# Laser_Harp_PCB.net
KiCad netlist of a schematic drawn in EAGLE
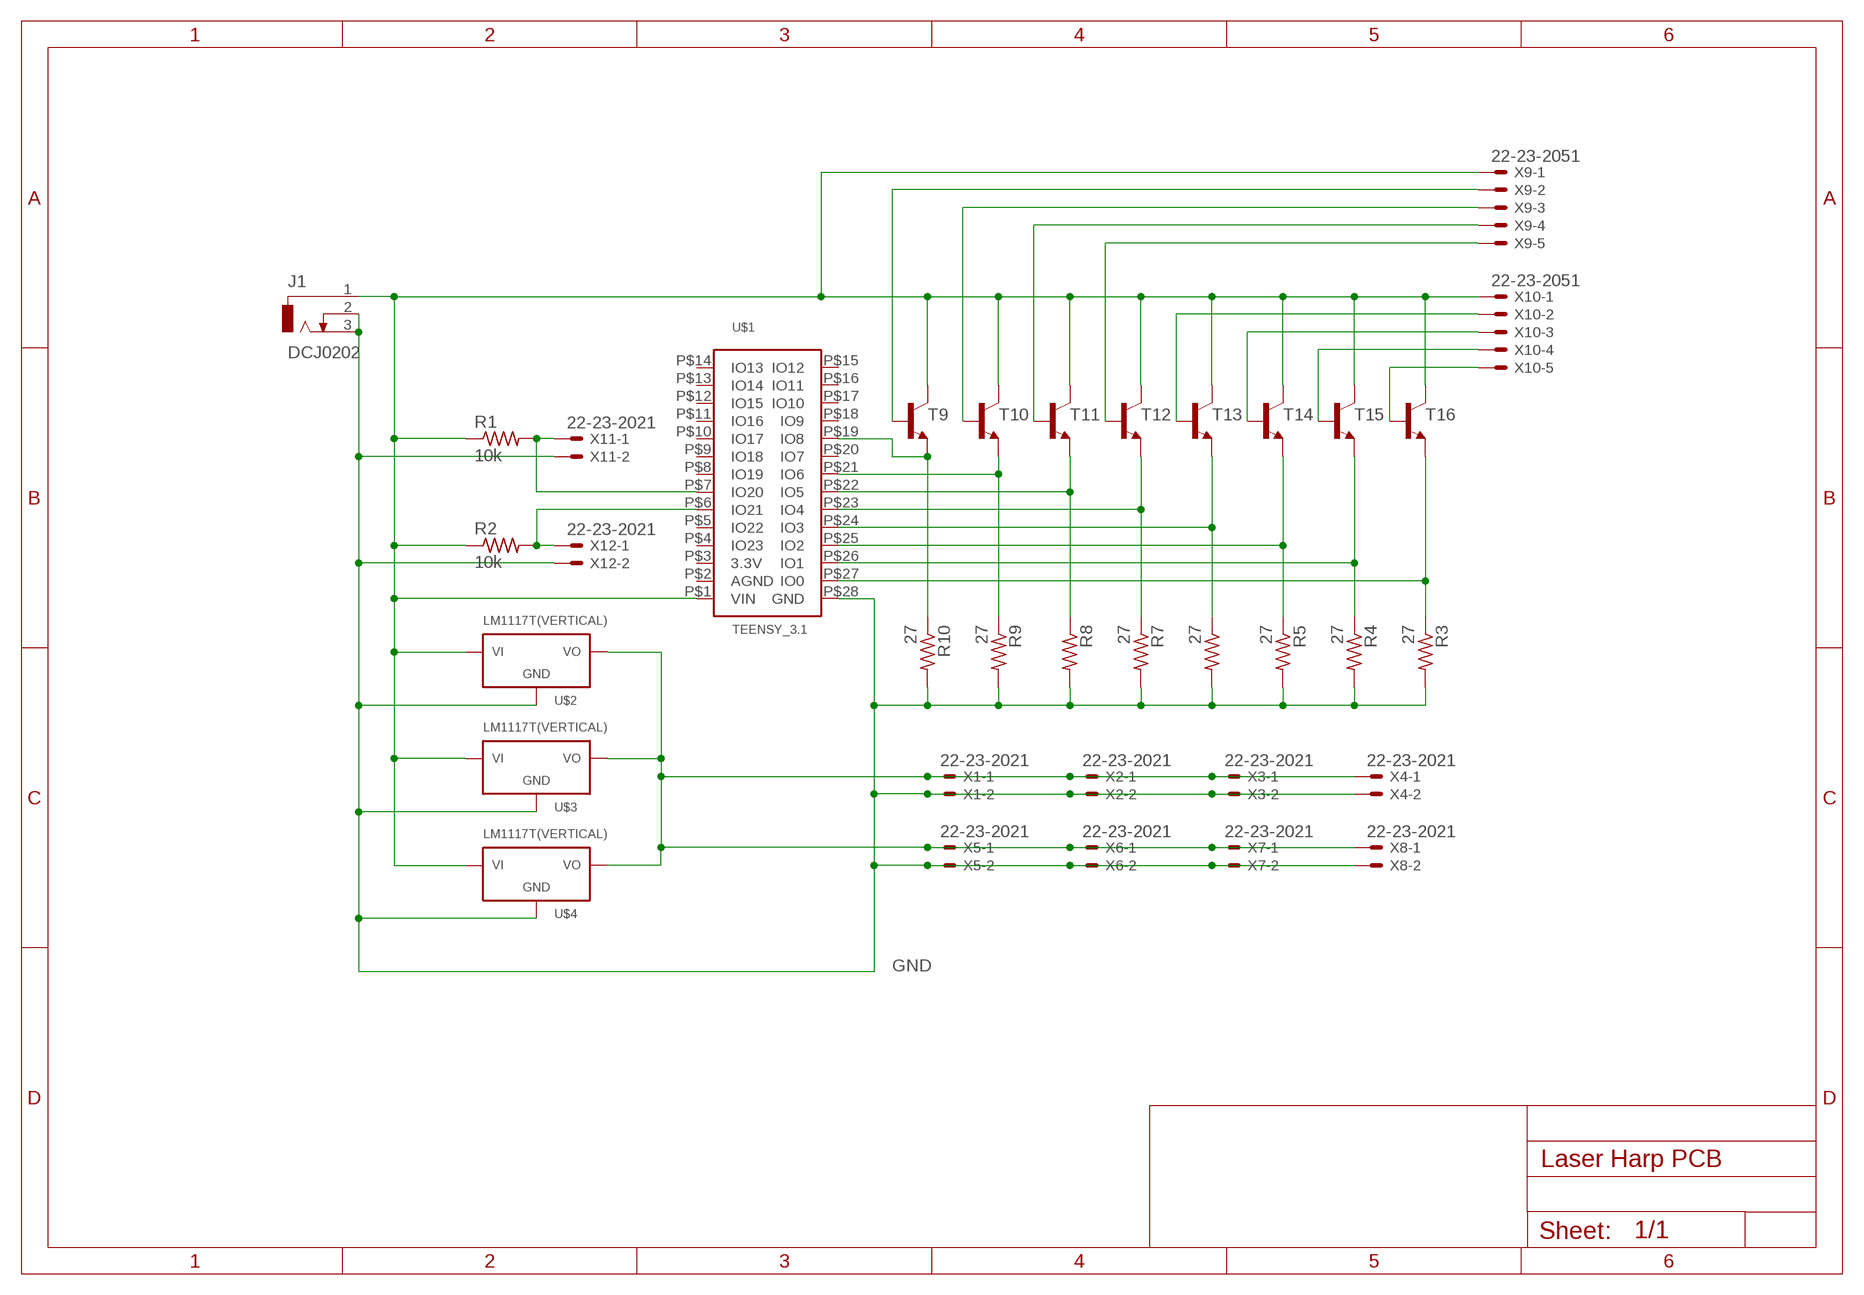
[diagram p0: schematic, sheet 1]

(export (version "E")
  (design (tool "Eeschema 10.0.6"))
  (components
    (comp (ref "J1")
      (value "DCJ0202")
      (footprint "eagle-import:DCJ0202")
      (libsource (lib "eagle-import") (part "DCJ0202"))
    )
    (comp (ref "R1")
      (value "10k")
      (footprint "eagle-import:0207_7")
      (libsource (lib "eagle-import") (part "R-US_0207/7"))
    )
    (comp (ref "R2")
      (value "10k")
      (footprint "eagle-import:0207_7")
      (libsource (lib "eagle-import") (part "R-US_0207/7"))
    )
    (comp (ref "R3")
      (value "27")
      (footprint "eagle-import:0207_7")
      (libsource (lib "eagle-import") (part "R-US_0207/7"))
    )
    (comp (ref "R4")
      (value "27")
      (footprint "eagle-import:0207_7")
      (libsource (lib "eagle-import") (part "R-US_0207/7"))
    )
    (comp (ref "R5")
      (value "27")
      (footprint "eagle-import:0207_7")
      (libsource (lib "eagle-import") (part "R-US_0207/7"))
    )
    (comp (ref "R6")
      (value "27")
      (footprint "eagle-import:0207_7")
      (libsource (lib "eagle-import") (part "R-US_0207/7"))
    )
    (comp (ref "R7")
      (value "27")
      (footprint "eagle-import:0207_7")
      (libsource (lib "eagle-import") (part "R-US_0207/7"))
    )
    (comp (ref "R8")
      (value "27")
      (footprint "eagle-import:0207_7")
      (libsource (lib "eagle-import") (part "R-US_0207/7"))
    )
    (comp (ref "R9")
      (value "27")
      (footprint "eagle-import:0207_7")
      (libsource (lib "eagle-import") (part "R-US_0207/7"))
    )
    (comp (ref "R10")
      (value "27")
      (footprint "eagle-import:0207_7")
      (libsource (lib "eagle-import") (part "R-US_0207/7"))
    )
    (comp (ref "T9")
      (value "2N3904-NPN-TO92-EBC")
      (footprint "eagle-import:TO92-EBC")
      (libsource (lib "eagle-import") (part "-NPN-TO92-EBC2N3904"))
    )
    (comp (ref "T10")
      (value "2N3904-NPN-TO92-EBC")
      (footprint "eagle-import:TO92-EBC")
      (libsource (lib "eagle-import") (part "-NPN-TO92-EBC2N3904"))
    )
    (comp (ref "T11")
      (value "2N3904-NPN-TO92-EBC")
      (footprint "eagle-import:TO92-EBC")
      (libsource (lib "eagle-import") (part "-NPN-TO92-EBC2N3904"))
    )
    (comp (ref "T12")
      (value "2N3904-NPN-TO92-EBC")
      (footprint "eagle-import:TO92-EBC")
      (libsource (lib "eagle-import") (part "-NPN-TO92-EBC2N3904"))
    )
    (comp (ref "T13")
      (value "2N3904-NPN-TO92-EBC")
      (footprint "eagle-import:TO92-EBC")
      (libsource (lib "eagle-import") (part "-NPN-TO92-EBC2N3904"))
    )
    (comp (ref "T14")
      (value "2N3904-NPN-TO92-EBC")
      (footprint "eagle-import:TO92-EBC")
      (libsource (lib "eagle-import") (part "-NPN-TO92-EBC2N3904"))
    )
    (comp (ref "T15")
      (value "2N3904-NPN-TO92-EBC")
      (footprint "eagle-import:TO92-EBC")
      (libsource (lib "eagle-import") (part "-NPN-TO92-EBC2N3904"))
    )
    (comp (ref "T16")
      (value "2N3904-NPN-TO92-EBC")
      (footprint "eagle-import:TO92-EBC")
      (libsource (lib "eagle-import") (part "-NPN-TO92-EBC2N3904"))
    )
    (comp (ref "U$1")
      (value "TEENSY_3.1")
      (footprint "eagle-import:TEENSY_3.1")
      (libsource (lib "eagle-import") (part "TEENSY_3.1"))
    )
    (comp (ref "U$2")
      (value "LM1117T(VERTICAL)")
      (footprint "eagle-import:317TS")
      (libsource (lib "eagle-import") (part "LM1117T(VERTICAL)"))
    )
    (comp (ref "U$3")
      (value "LM1117T(VERTICAL)")
      (footprint "eagle-import:317TS")
      (libsource (lib "eagle-import") (part "LM1117T(VERTICAL)"))
    )
    (comp (ref "U$4")
      (value "LM1117T(VERTICAL)")
      (footprint "eagle-import:317TS")
      (libsource (lib "eagle-import") (part "LM1117T(VERTICAL)"))
    )
    (comp (ref "X1")
      (value "22-23-2021")
      (footprint "eagle-import:22-23-2021")
      (fields (field (name "MF") "MOLEX"))
      (libsource (lib "eagle-import") (part "22-23-2021"))
    )
    (comp (ref "X2")
      (value "22-23-2021")
      (footprint "eagle-import:22-23-2021")
      (fields (field (name "MF") "MOLEX"))
      (libsource (lib "eagle-import") (part "22-23-2021"))
    )
    (comp (ref "X3")
      (value "22-23-2021")
      (footprint "eagle-import:22-23-2021")
      (fields (field (name "MF") "MOLEX"))
      (libsource (lib "eagle-import") (part "22-23-2021"))
    )
    (comp (ref "X4")
      (value "22-23-2021")
      (footprint "eagle-import:22-23-2021")
      (fields (field (name "MF") "MOLEX"))
      (libsource (lib "eagle-import") (part "22-23-2021"))
    )
    (comp (ref "X5")
      (value "22-23-2021")
      (footprint "eagle-import:22-23-2021")
      (fields (field (name "MF") "MOLEX"))
      (libsource (lib "eagle-import") (part "22-23-2021"))
    )
    (comp (ref "X6")
      (value "22-23-2021")
      (footprint "eagle-import:22-23-2021")
      (fields (field (name "MF") "MOLEX"))
      (libsource (lib "eagle-import") (part "22-23-2021"))
    )
    (comp (ref "X7")
      (value "22-23-2021")
      (footprint "eagle-import:22-23-2021")
      (fields (field (name "MF") "MOLEX"))
      (libsource (lib "eagle-import") (part "22-23-2021"))
    )
    (comp (ref "X8")
      (value "22-23-2021")
      (footprint "eagle-import:22-23-2021")
      (fields (field (name "MF") "MOLEX"))
      (libsource (lib "eagle-import") (part "22-23-2021"))
    )
    (comp (ref "X9")
      (value "22-23-2051")
      (footprint "eagle-import:22-23-2051")
      (fields (field (name "MF") "MOLEX"))
      (libsource (lib "eagle-import") (part "22-23-2051"))
    )
    (comp (ref "X10")
      (value "22-23-2051")
      (footprint "eagle-import:22-23-2051")
      (fields (field (name "MF") "MOLEX"))
      (libsource (lib "eagle-import") (part "22-23-2051"))
    )
    (comp (ref "X11")
      (value "22-23-2021")
      (footprint "eagle-import:22-23-2021")
      (fields (field (name "MF") "MOLEX"))
      (libsource (lib "eagle-import") (part "22-23-2021"))
    )
    (comp (ref "X12")
      (value "22-23-2021")
      (footprint "eagle-import:22-23-2021")
      (fields (field (name "MF") "MOLEX"))
      (libsource (lib "eagle-import") (part "22-23-2021"))
    )
  )
  (nets
    (net (code "1") (name "/GND") (class "Default")
      (node (ref "J1") (pin "2") (pinfunction "2_2") (pintype "passive"))
      (node (ref "J1") (pin "3") (pinfunction "3_3") (pintype "passive"))
      (node (ref "R10") (pin "2") (pinfunction "2_2") (pintype "passive"))
      (node (ref "R3") (pin "2") (pinfunction "2_2") (pintype "passive"))
      (node (ref "R4") (pin "2") (pinfunction "2_2") (pintype "passive"))
      (node (ref "R5") (pin "2") (pinfunction "2_2") (pintype "passive"))
      (node (ref "R6") (pin "2") (pinfunction "2_2") (pintype "passive"))
      (node (ref "R7") (pin "2") (pinfunction "2_2") (pintype "passive"))
      (node (ref "R8") (pin "2") (pinfunction "2_2") (pintype "passive"))
      (node (ref "R9") (pin "2") (pinfunction "2_2") (pintype "passive"))
      (node (ref "U$1") (pin "P$28") (pinfunction "GND_P$28") (pintype "bidirectional"))
      (node (ref "U$2") (pin "1") (pinfunction "GND_1") (pintype "bidirectional"))
      (node (ref "U$3") (pin "1") (pinfunction "GND_1") (pintype "bidirectional"))
      (node (ref "U$4") (pin "1") (pinfunction "GND_1") (pintype "bidirectional"))
      (node (ref "X1") (pin "2") (pinfunction "S_2") (pintype "passive"))
      (node (ref "X11") (pin "2") (pinfunction "S_2") (pintype "passive"))
      (node (ref "X12") (pin "2") (pinfunction "S_2") (pintype "passive"))
      (node (ref "X2") (pin "2") (pinfunction "S_2") (pintype "passive"))
      (node (ref "X3") (pin "2") (pinfunction "S_2") (pintype "passive"))
      (node (ref "X4") (pin "2") (pinfunction "S_2") (pintype "passive"))
      (node (ref "X5") (pin "2") (pinfunction "S_2") (pintype "passive"))
      (node (ref "X6") (pin "2") (pinfunction "S_2") (pintype "passive"))
      (node (ref "X7") (pin "2") (pinfunction "S_2") (pintype "passive"))
      (node (ref "X8") (pin "2") (pinfunction "S_2") (pintype "passive"))
    )
    (net (code "2") (name "Net-(U$1-IO0)") (class "Default")
      (node (ref "R3") (pin "1") (pinfunction "1_1") (pintype "passive"))
      (node (ref "T16") (pin "E") (pinfunction "E_E") (pintype "passive"))
      (node (ref "U$1") (pin "P$27") (pinfunction "IO0_P$27") (pintype "bidirectional"))
    )
    (net (code "3") (name "Net-(U$1-IO1)") (class "Default")
      (node (ref "R4") (pin "1") (pinfunction "1_1") (pintype "passive"))
      (node (ref "T15") (pin "E") (pinfunction "E_E") (pintype "passive"))
      (node (ref "U$1") (pin "P$26") (pinfunction "IO1_P$26") (pintype "bidirectional"))
    )
    (net (code "4") (name "Net-(U$1-IO2)") (class "Default")
      (node (ref "R5") (pin "1") (pinfunction "1_1") (pintype "passive"))
      (node (ref "T14") (pin "E") (pinfunction "E_E") (pintype "passive"))
      (node (ref "U$1") (pin "P$25") (pinfunction "IO2_P$25") (pintype "bidirectional"))
    )
    (net (code "5") (name "Net-(U$1-IO3)") (class "Default")
      (node (ref "R6") (pin "1") (pinfunction "1_1") (pintype "passive"))
      (node (ref "T13") (pin "E") (pinfunction "E_E") (pintype "passive"))
      (node (ref "U$1") (pin "P$24") (pinfunction "IO3_P$24") (pintype "bidirectional"))
    )
    (net (code "6") (name "Net-(U$1-IO4)") (class "Default")
      (node (ref "R7") (pin "1") (pinfunction "1_1") (pintype "passive"))
      (node (ref "T12") (pin "E") (pinfunction "E_E") (pintype "passive"))
      (node (ref "U$1") (pin "P$23") (pinfunction "IO4_P$23") (pintype "bidirectional"))
    )
    (net (code "7") (name "Net-(U$1-IO5)") (class "Default")
      (node (ref "R8") (pin "1") (pinfunction "1_1") (pintype "passive"))
      (node (ref "T11") (pin "E") (pinfunction "E_E") (pintype "passive"))
      (node (ref "U$1") (pin "P$22") (pinfunction "IO5_P$22") (pintype "bidirectional"))
    )
    (net (code "8") (name "Net-(U$1-IO6)") (class "Default")
      (node (ref "R9") (pin "1") (pinfunction "1_1") (pintype "passive"))
      (node (ref "T10") (pin "E") (pinfunction "E_E") (pintype "passive"))
      (node (ref "U$1") (pin "P$21") (pinfunction "IO6_P$21") (pintype "bidirectional"))
    )
    (net (code "9") (name "Net-(U$1-IO8)") (class "Default")
      (node (ref "R10") (pin "1") (pinfunction "1_1") (pintype "passive"))
      (node (ref "T9") (pin "E") (pinfunction "E_E") (pintype "passive"))
      (node (ref "U$1") (pin "P$19") (pinfunction "IO8_P$19") (pintype "bidirectional"))
    )
    (net (code "10") (name "Net-(U$1-IO20)") (class "Default")
      (node (ref "R1") (pin "2") (pinfunction "2_2") (pintype "passive"))
      (node (ref "U$1") (pin "P$7") (pinfunction "IO20_P$7") (pintype "bidirectional"))
      (node (ref "X11") (pin "1") (pinfunction "S_1") (pintype "passive"))
    )
    (net (code "11") (name "Net-(U$1-IO21)") (class "Default")
      (node (ref "R2") (pin "2") (pinfunction "2_2") (pintype "passive"))
      (node (ref "U$1") (pin "P$6") (pinfunction "IO21_P$6") (pintype "bidirectional"))
      (node (ref "X12") (pin "1") (pinfunction "S_1") (pintype "passive"))
    )
    (net (code "12") (name "Net-(U$1-VIN)") (class "Default")
      (node (ref "J1") (pin "1") (pinfunction "1_1") (pintype "passive"))
      (node (ref "R1") (pin "1") (pinfunction "1_1") (pintype "passive"))
      (node (ref "R2") (pin "1") (pinfunction "1_1") (pintype "passive"))
      (node (ref "T10") (pin "C") (pinfunction "C_C") (pintype "passive"))
      (node (ref "T11") (pin "C") (pinfunction "C_C") (pintype "passive"))
      (node (ref "T12") (pin "C") (pinfunction "C_C") (pintype "passive"))
      (node (ref "T13") (pin "C") (pinfunction "C_C") (pintype "passive"))
      (node (ref "T14") (pin "C") (pinfunction "C_C") (pintype "passive"))
      (node (ref "T15") (pin "C") (pinfunction "C_C") (pintype "passive"))
      (node (ref "T16") (pin "C") (pinfunction "C_C") (pintype "passive"))
      (node (ref "T9") (pin "C") (pinfunction "C_C") (pintype "passive"))
      (node (ref "U$1") (pin "P$1") (pinfunction "VIN_P$1") (pintype "bidirectional"))
      (node (ref "U$2") (pin "3") (pinfunction "VIN_3") (pintype "bidirectional"))
      (node (ref "U$3") (pin "3") (pinfunction "VIN_3") (pintype "bidirectional"))
      (node (ref "U$4") (pin "3") (pinfunction "VIN_3") (pintype "bidirectional"))
      (node (ref "X10") (pin "1") (pinfunction "S_1") (pintype "passive"))
      (node (ref "X9") (pin "1") (pinfunction "S_1") (pintype "passive"))
    )
    (net (code "13") (name "Net-(U$2-VOUT)") (class "Default")
      (node (ref "U$2") (pin "2") (pinfunction "VOUT_2") (pintype "bidirectional"))
      (node (ref "U$3") (pin "2") (pinfunction "VOUT_2") (pintype "bidirectional"))
      (node (ref "U$4") (pin "2") (pinfunction "VOUT_2") (pintype "bidirectional"))
      (node (ref "X1") (pin "1") (pinfunction "S_1") (pintype "passive"))
      (node (ref "X2") (pin "1") (pinfunction "S_1") (pintype "passive"))
      (node (ref "X3") (pin "1") (pinfunction "S_1") (pintype "passive"))
      (node (ref "X4") (pin "1") (pinfunction "S_1") (pintype "passive"))
      (node (ref "X5") (pin "1") (pinfunction "S_1") (pintype "passive"))
      (node (ref "X6") (pin "1") (pinfunction "S_1") (pintype "passive"))
      (node (ref "X7") (pin "1") (pinfunction "S_1") (pintype "passive"))
      (node (ref "X8") (pin "1") (pinfunction "S_1") (pintype "passive"))
    )
    (net (code "14") (name "Net-(X9B-S)") (class "Default")
      (node (ref "T9") (pin "B") (pinfunction "B_B") (pintype "passive"))
      (node (ref "X9") (pin "2") (pinfunction "S_2") (pintype "passive"))
    )
    (net (code "15") (name "Net-(X9C-S)") (class "Default")
      (node (ref "T10") (pin "B") (pinfunction "B_B") (pintype "passive"))
      (node (ref "X9") (pin "3") (pinfunction "S_3") (pintype "passive"))
    )
    (net (code "16") (name "Net-(X9D-S)") (class "Default")
      (node (ref "T11") (pin "B") (pinfunction "B_B") (pintype "passive"))
      (node (ref "X9") (pin "4") (pinfunction "S_4") (pintype "passive"))
    )
    (net (code "17") (name "Net-(X9E-S)") (class "Default")
      (node (ref "T12") (pin "B") (pinfunction "B_B") (pintype "passive"))
      (node (ref "X9") (pin "5") (pinfunction "S_5") (pintype "passive"))
    )
    (net (code "18") (name "Net-(X10B-S)") (class "Default")
      (node (ref "T13") (pin "B") (pinfunction "B_B") (pintype "passive"))
      (node (ref "X10") (pin "2") (pinfunction "S_2") (pintype "passive"))
    )
    (net (code "19") (name "Net-(X10C-S)") (class "Default")
      (node (ref "T14") (pin "B") (pinfunction "B_B") (pintype "passive"))
      (node (ref "X10") (pin "3") (pinfunction "S_3") (pintype "passive"))
    )
    (net (code "20") (name "Net-(X10D-S)") (class "Default")
      (node (ref "T15") (pin "B") (pinfunction "B_B") (pintype "passive"))
      (node (ref "X10") (pin "4") (pinfunction "S_4") (pintype "passive"))
    )
    (net (code "21") (name "Net-(X10E-S)") (class "Default")
      (node (ref "T16") (pin "B") (pinfunction "B_B") (pintype "passive"))
      (node (ref "X10") (pin "5") (pinfunction "S_5") (pintype "passive"))
    )
    (net (code "22") (name "unconnected-(U$1-3.3V-PadP$3)") (class "Default")
      (node (ref "U$1") (pin "P$3") (pinfunction "3.3V_P$3") (pintype "bidirectional"))
    )
    (net (code "23") (name "unconnected-(U$1-AGND-PadP$2)") (class "Default")
      (node (ref "U$1") (pin "P$2") (pinfunction "AGND_P$2") (pintype "bidirectional"))
    )
    (net (code "24") (name "unconnected-(U$1-IO7-PadP$20)") (class "Default")
      (node (ref "U$1") (pin "P$20") (pinfunction "IO7_P$20") (pintype "bidirectional"))
    )
    (net (code "25") (name "unconnected-(U$1-IO9-PadP$18)") (class "Default")
      (node (ref "U$1") (pin "P$18") (pinfunction "IO9_P$18") (pintype "bidirectional"))
    )
    (net (code "26") (name "unconnected-(U$1-IO10-PadP$17)") (class "Default")
      (node (ref "U$1") (pin "P$17") (pinfunction "IO10_P$17") (pintype "bidirectional"))
    )
    (net (code "27") (name "unconnected-(U$1-IO11-PadP$16)") (class "Default")
      (node (ref "U$1") (pin "P$16") (pinfunction "IO11_P$16") (pintype "bidirectional"))
    )
    (net (code "28") (name "unconnected-(U$1-IO12-PadP$15)") (class "Default")
      (node (ref "U$1") (pin "P$15") (pinfunction "IO12_P$15") (pintype "bidirectional"))
    )
    (net (code "29") (name "unconnected-(U$1-IO13-PadP$14)") (class "Default")
      (node (ref "U$1") (pin "P$14") (pinfunction "IO13_P$14") (pintype "bidirectional"))
    )
    (net (code "30") (name "unconnected-(U$1-IO14-PadP$13)") (class "Default")
      (node (ref "U$1") (pin "P$13") (pinfunction "IO14_P$13") (pintype "bidirectional"))
    )
    (net (code "31") (name "unconnected-(U$1-IO15-PadP$12)") (class "Default")
      (node (ref "U$1") (pin "P$12") (pinfunction "IO15_P$12") (pintype "bidirectional"))
    )
    (net (code "32") (name "unconnected-(U$1-IO16-PadP$11)") (class "Default")
      (node (ref "U$1") (pin "P$11") (pinfunction "IO16_P$11") (pintype "bidirectional"))
    )
    (net (code "33") (name "unconnected-(U$1-IO17-PadP$10)") (class "Default")
      (node (ref "U$1") (pin "P$10") (pinfunction "IO17_P$10") (pintype "bidirectional"))
    )
    (net (code "34") (name "unconnected-(U$1-IO18-PadP$9)") (class "Default")
      (node (ref "U$1") (pin "P$9") (pinfunction "IO18_P$9") (pintype "bidirectional"))
    )
    (net (code "35") (name "unconnected-(U$1-IO19-PadP$8)") (class "Default")
      (node (ref "U$1") (pin "P$8") (pinfunction "IO19_P$8") (pintype "bidirectional"))
    )
    (net (code "36") (name "unconnected-(U$1-IO22-PadP$5)") (class "Default")
      (node (ref "U$1") (pin "P$5") (pinfunction "IO22_P$5") (pintype "bidirectional"))
    )
    (net (code "37") (name "unconnected-(U$1-IO23-PadP$4)") (class "Default")
      (node (ref "U$1") (pin "P$4") (pinfunction "IO23_P$4") (pintype "bidirectional"))
    )
  )
)
